# 15_1.net
KiCad netlist of a schematic drawn in EasyEDA Pro
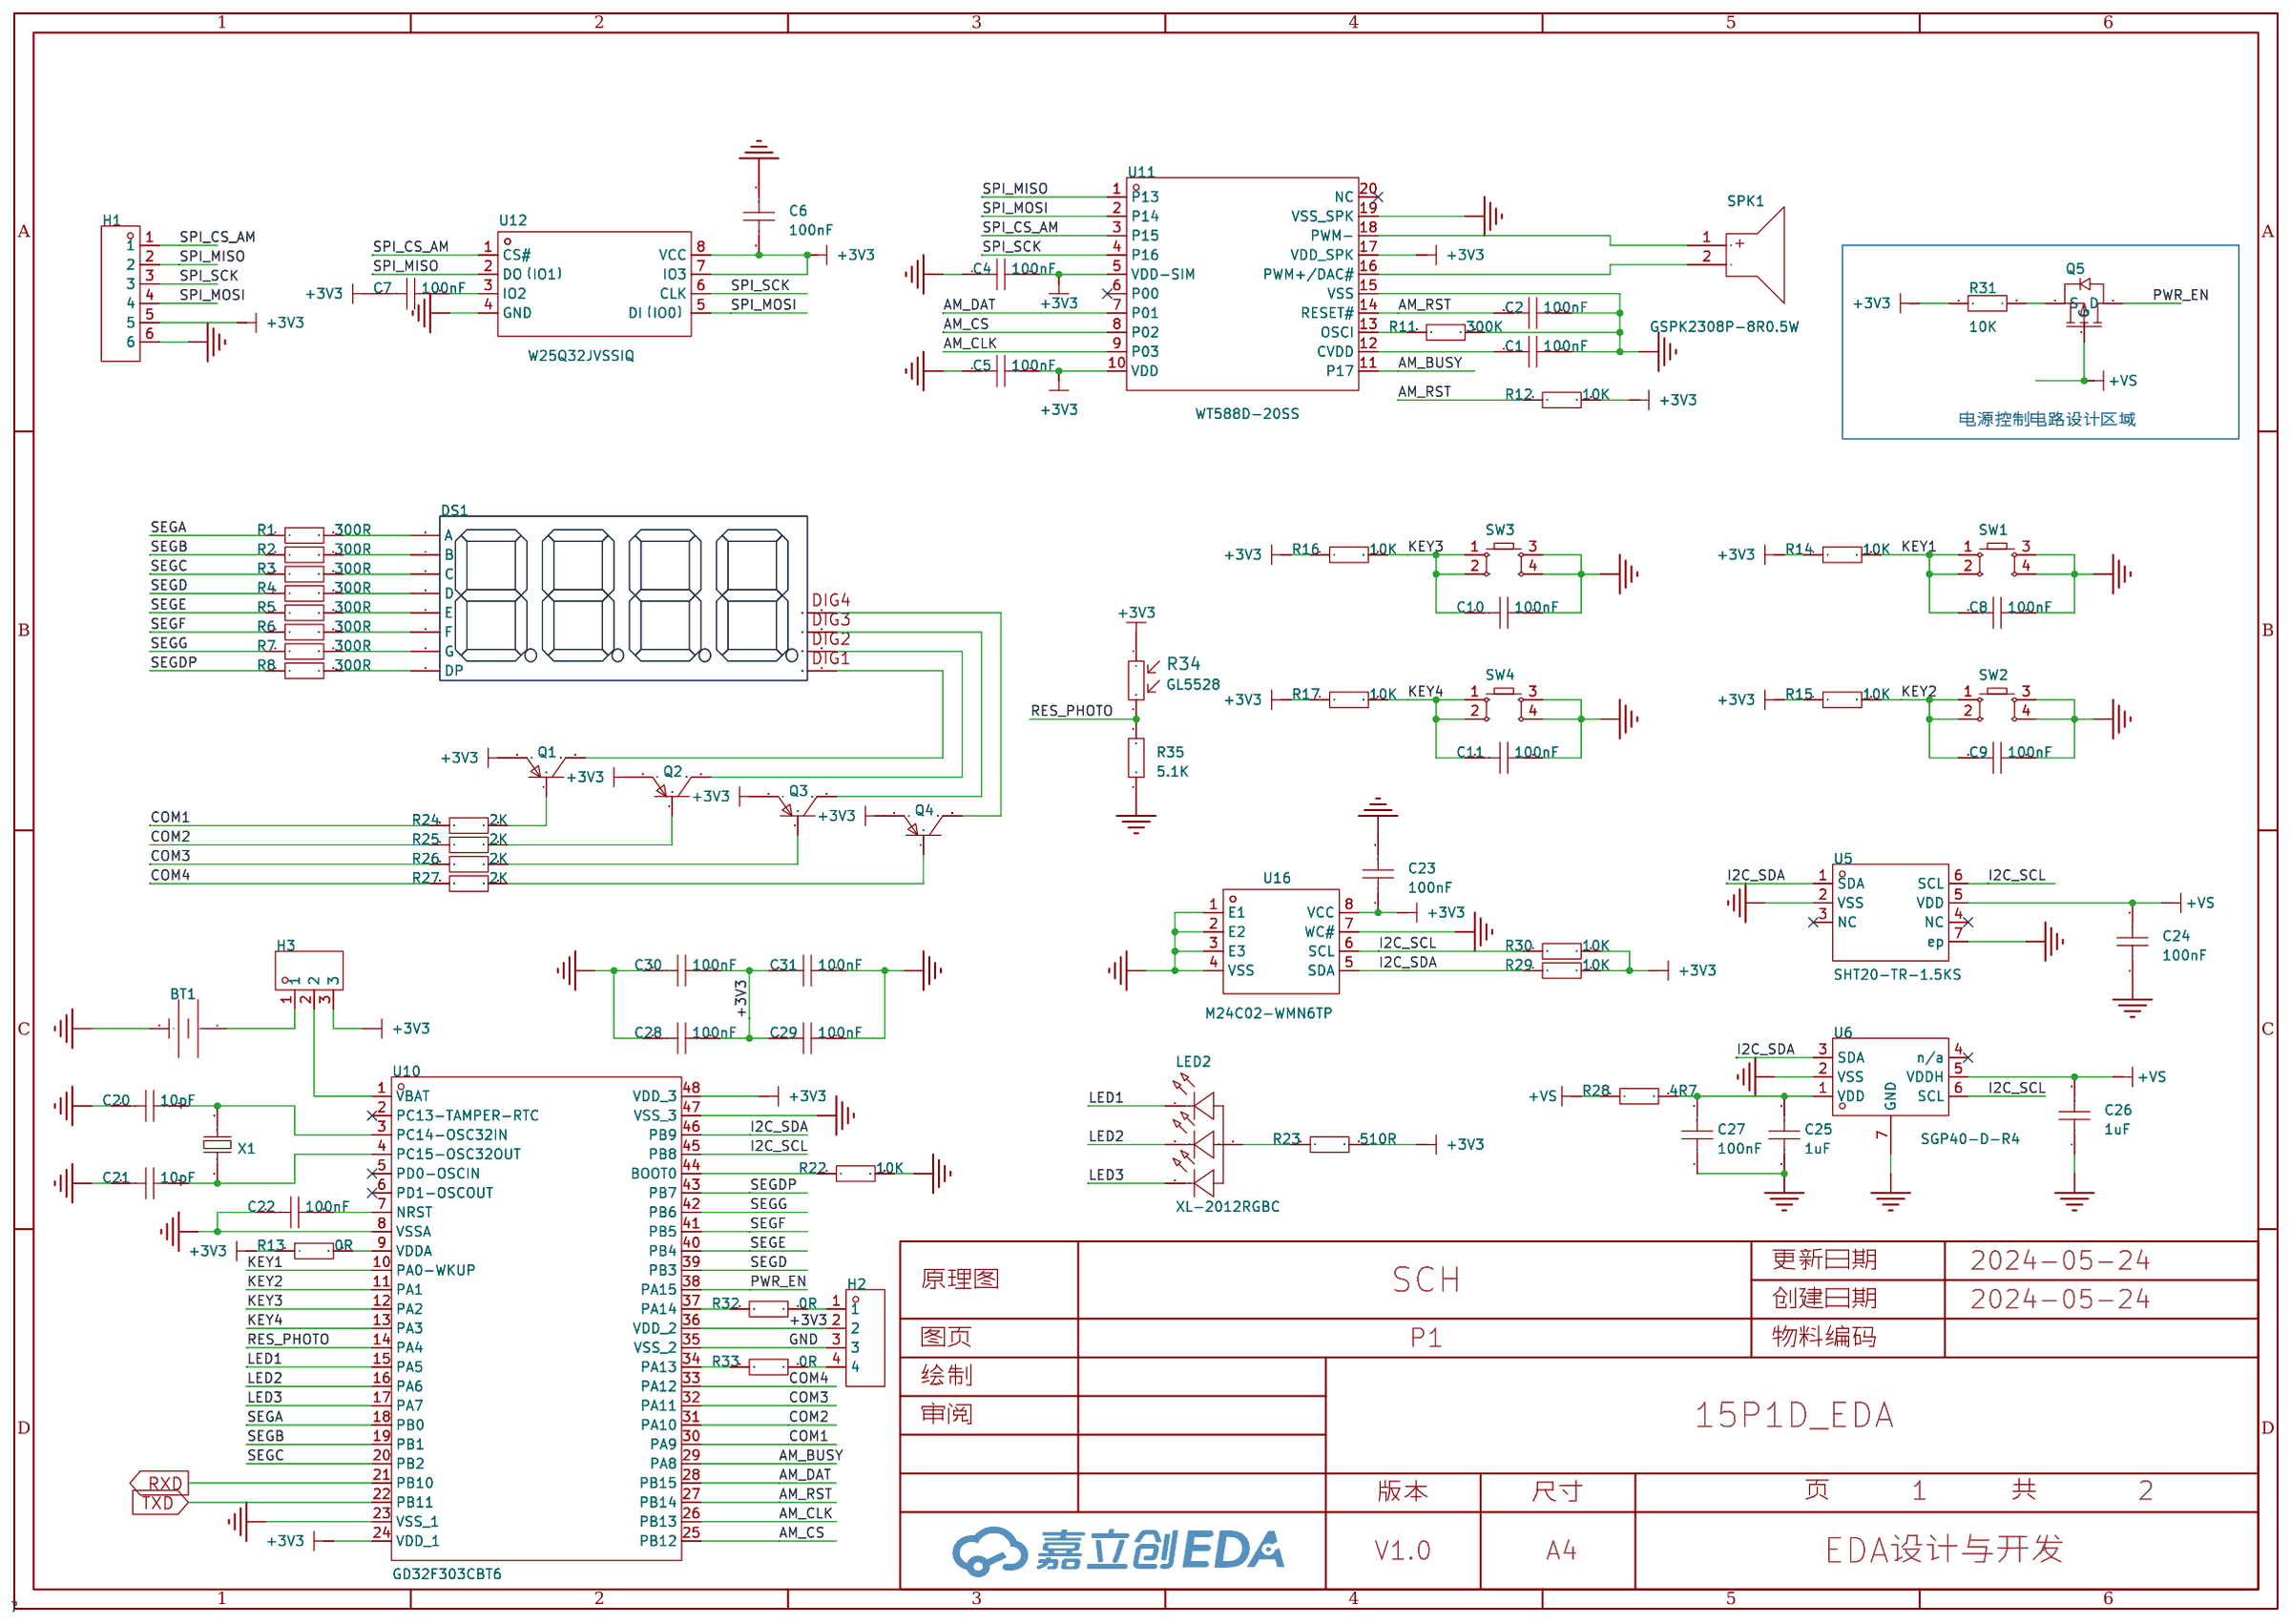
[diagram p0: P1]
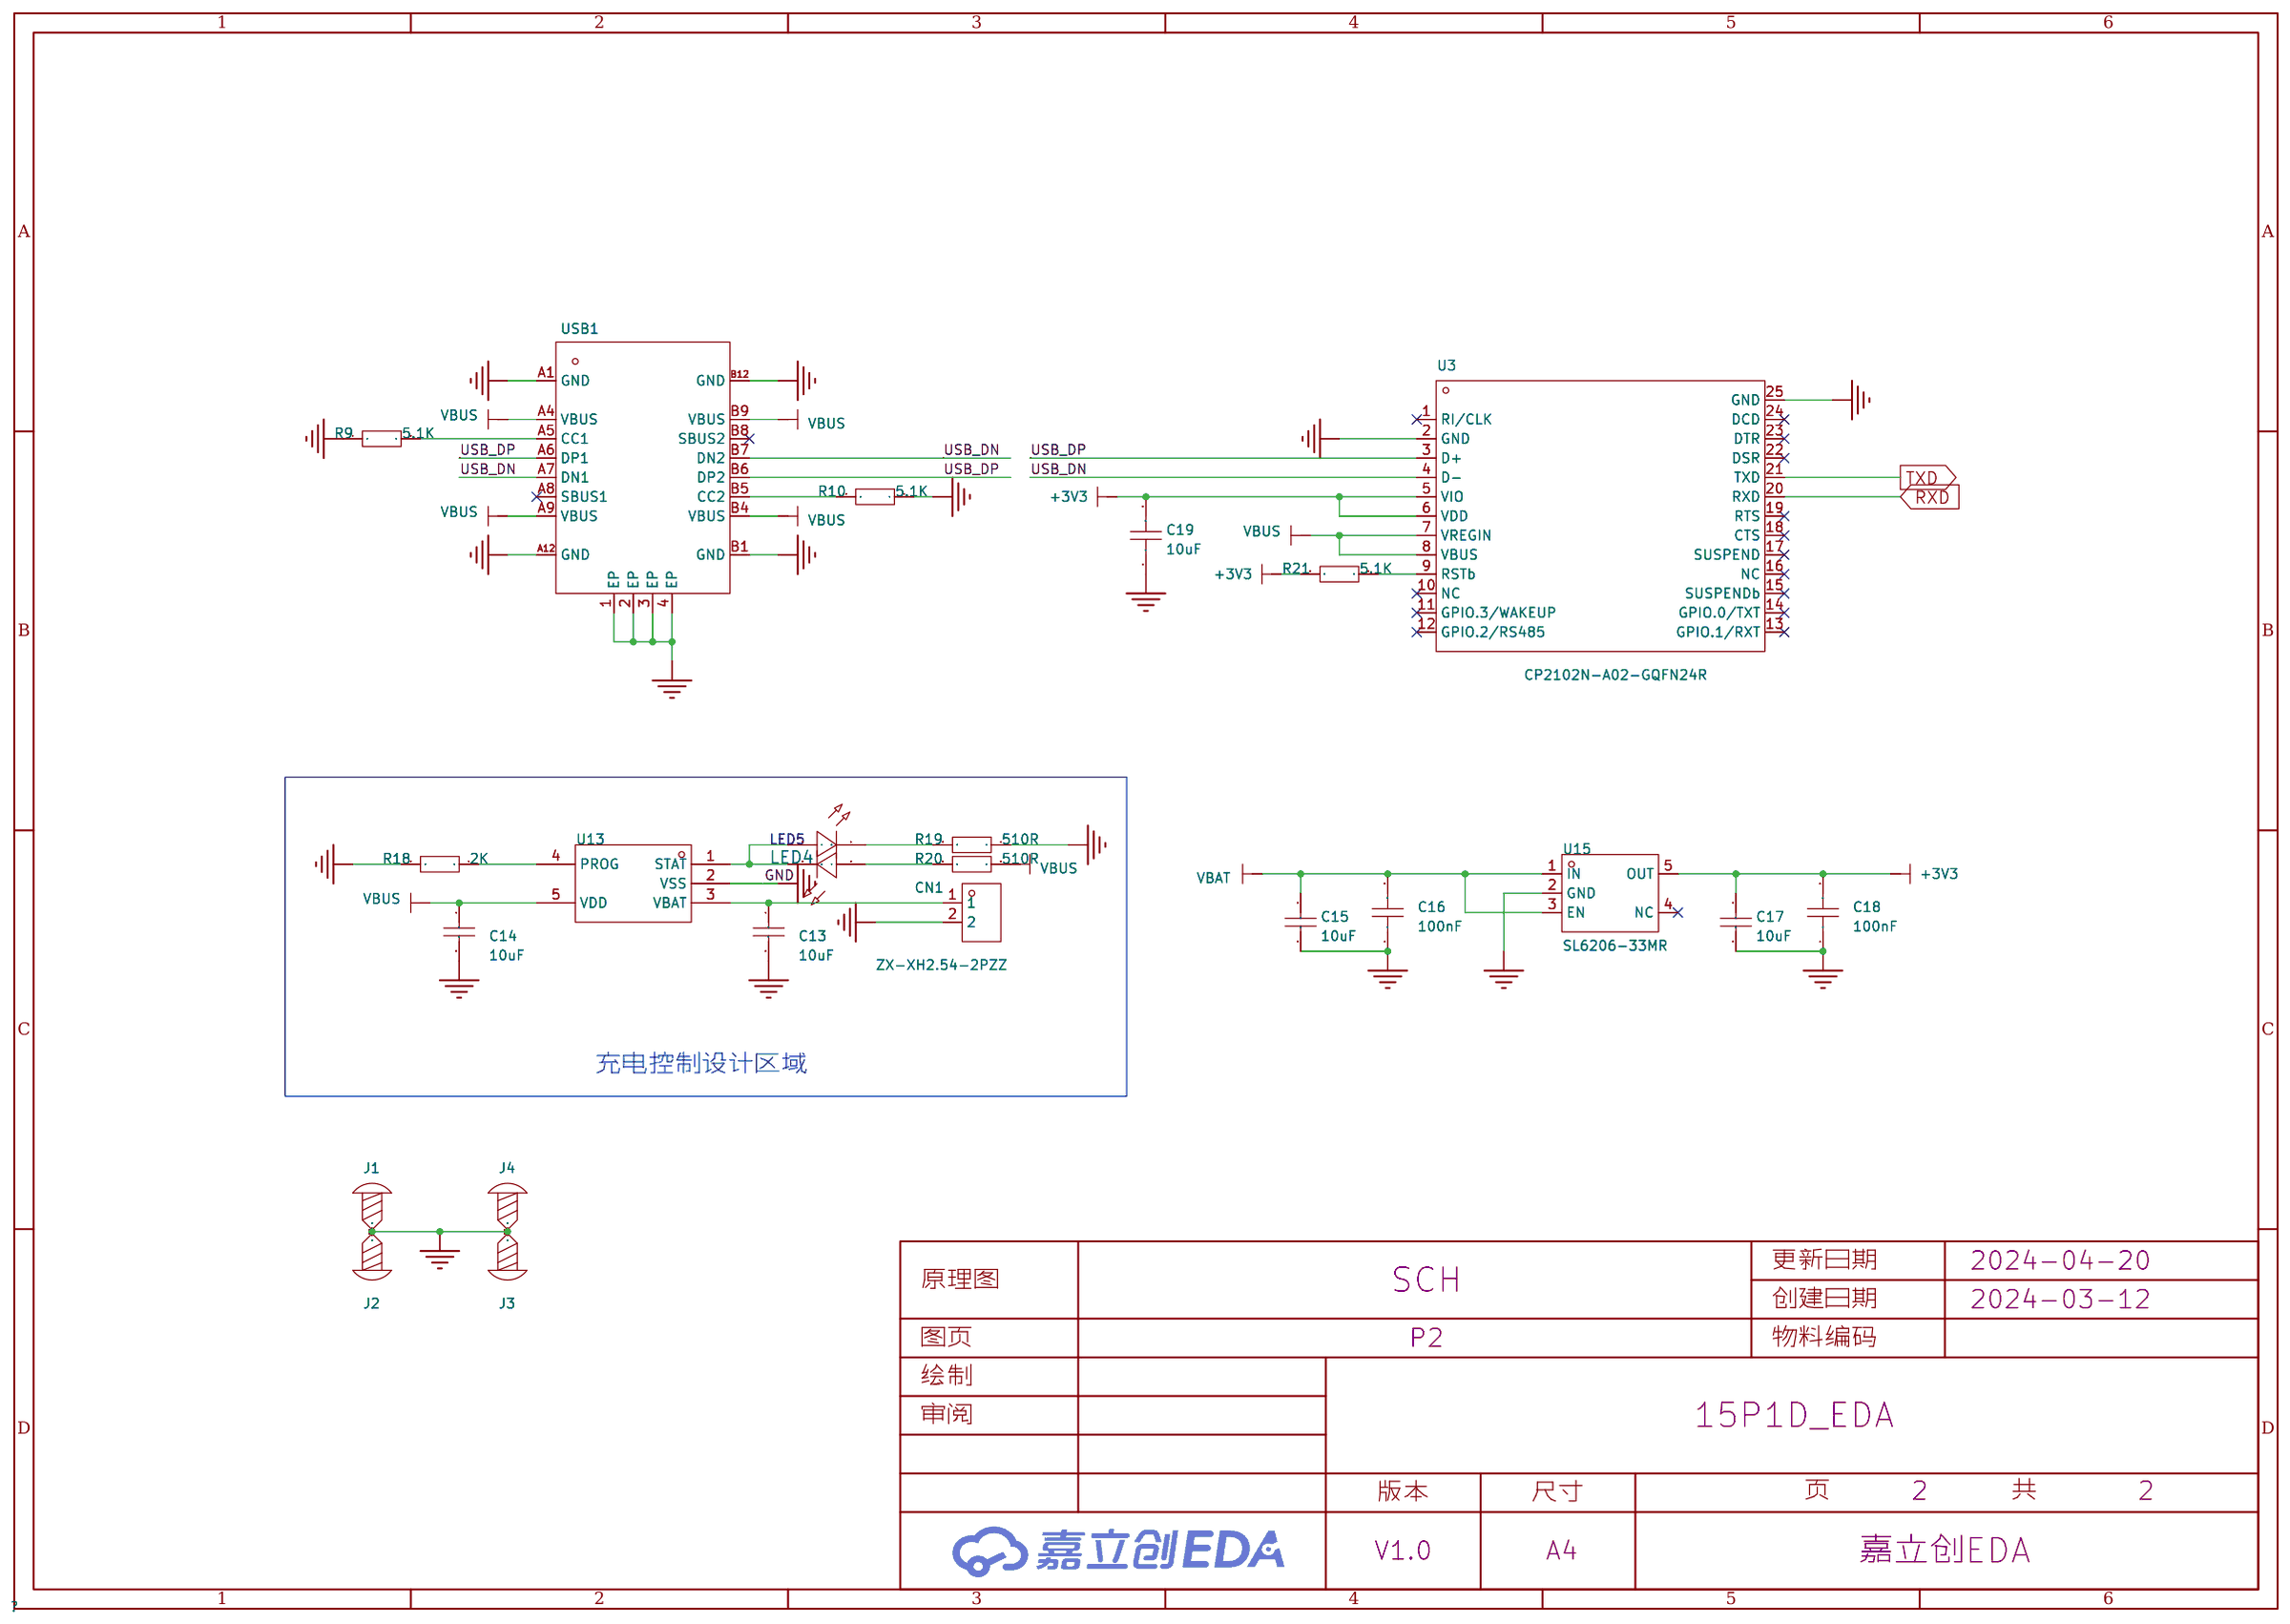
[diagram p1: P2]

(export (version "E")
  (design (tool "Eeschema 10.0.6"))
  (components
    (comp (ref "BT1")
      (value "BS-12-B3AA003")
      (footprint "easyedapro:BAT-SMD_BS-12-B3AA011")
      (description "连接器类型:电池底座;适用电池规格:CR1220;工作温度范围:-25°C~+85°C;")
      (fields (field (name "Manufacturer") "MYOUNG(美阳)"))
      (libsource (lib "easyedapro") (part "BS-12-B3AA003"))
    )
    (comp (ref "C1")
      (value "100nF")
      (footprint "easyedapro:C0805")
      (libsource (lib "easyedapro") (part "CapAcitance"))
    )
    (comp (ref "C2")
      (value "100nF")
      (footprint "easyedapro:C0805")
      (libsource (lib "easyedapro") (part "CapAcitance"))
    )
    (comp (ref "C4")
      (value "100nF")
      (footprint "easyedapro:C0805")
      (libsource (lib "easyedapro") (part "CapAcitance"))
    )
    (comp (ref "C5")
      (value "100nF")
      (footprint "easyedapro:C0805")
      (libsource (lib "easyedapro") (part "CapAcitance"))
    )
    (comp (ref "C6")
      (value "100nF")
      (footprint "easyedapro:C0805")
      (libsource (lib "easyedapro") (part "CapAcitance"))
    )
    (comp (ref "C7")
      (value "100nF")
      (footprint "easyedapro:C0805")
      (libsource (lib "easyedapro") (part "CapAcitance"))
    )
    (comp (ref "C8")
      (value "100nF")
      (footprint "easyedapro:C0805")
      (libsource (lib "easyedapro") (part "CapAcitance"))
    )
    (comp (ref "C9")
      (value "100nF")
      (footprint "easyedapro:C0805")
      (libsource (lib "easyedapro") (part "CapAcitance"))
    )
    (comp (ref "C10")
      (value "100nF")
      (footprint "easyedapro:C0805")
      (libsource (lib "easyedapro") (part "CapAcitance"))
    )
    (comp (ref "C11")
      (value "100nF")
      (footprint "easyedapro:C0805")
      (libsource (lib "easyedapro") (part "CapAcitance"))
    )
    (comp (ref "C20")
      (value "10pF")
      (footprint "easyedapro:C0805")
      (libsource (lib "easyedapro") (part "CapAcitance"))
    )
    (comp (ref "C21")
      (value "10pF")
      (footprint "easyedapro:C0805")
      (libsource (lib "easyedapro") (part "CapAcitance"))
    )
    (comp (ref "C22")
      (value "100nF")
      (footprint "easyedapro:C0805")
      (libsource (lib "easyedapro") (part "CapAcitance"))
    )
    (comp (ref "C23")
      (value "100nF")
      (footprint "easyedapro:C0805")
      (libsource (lib "easyedapro") (part "CapAcitance"))
    )
    (comp (ref "C24")
      (value "100nF")
      (footprint "easyedapro:C0805")
      (libsource (lib "easyedapro") (part "CapAcitance"))
    )
    (comp (ref "C25")
      (value "1uF")
      (footprint "easyedapro:C0805")
      (libsource (lib "easyedapro") (part "CapAcitance"))
    )
    (comp (ref "C26")
      (value "1uF")
      (footprint "easyedapro:C0805")
      (libsource (lib "easyedapro") (part "CapAcitance"))
    )
    (comp (ref "C27")
      (value "100nF")
      (footprint "easyedapro:C0805")
      (libsource (lib "easyedapro") (part "CapAcitance"))
    )
    (comp (ref "C28")
      (value "100nF")
      (footprint "easyedapro:C0805")
      (libsource (lib "easyedapro") (part "CapAcitance"))
    )
    (comp (ref "C29")
      (value "100nF")
      (footprint "easyedapro:C0805")
      (libsource (lib "easyedapro") (part "CapAcitance"))
    )
    (comp (ref "C30")
      (value "100nF")
      (footprint "easyedapro:C0805")
      (libsource (lib "easyedapro") (part "CapAcitance"))
    )
    (comp (ref "C31")
      (value "100nF")
      (footprint "easyedapro:C0805")
      (libsource (lib "easyedapro") (part "CapAcitance"))
    )
    (comp (ref "DS1")
      (value "~")
      (footprint "easyedapro:LED-SEG-TH_FJ5461AH")
      (libsource (lib "easyedapro") (part "LED_SEG_TH_0.56x4"))
    )
    (comp (ref "H1")
      (value "~")
      (footprint "easyedapro:HDR-TH_6P-P2.54-V-F")
      (libsource (lib "easyedapro") (part "Header-Female-2.54_1x6"))
    )
    (comp (ref "H2")
      (value "~")
      (footprint "easyedapro:HDR-TH_4P-P2.54-V-F")
      (libsource (lib "easyedapro") (part "2.54-1*4P母"))
    )
    (comp (ref "H3")
      (value "Jumper3")
      (footprint "easyedapro:HDR-TH_3P-P2.54-V-M-A")
      (libsource (lib "easyedapro") (part "JUMPER3"))
    )
    (comp (ref "LED2")
      (value "XL-2012RGBC")
      (footprint "easyedapro:LED-SMD_4P-L2.0-W1.3-BR")
      (fields (field (name "Manufacturer") "XINGLIGHT(成兴光)"))
      (libsource (lib "easyedapro") (part "XL-2012RGBC"))
    )
    (comp (ref "Q1")
      (value "~")
      (footprint "easyedapro:S8550P_SOT")
      (libsource (lib "easyedapro") (part "PNP"))
    )
    (comp (ref "Q2")
      (value "~")
      (footprint "easyedapro:S8550P_SOT")
      (libsource (lib "easyedapro") (part "PNP"))
    )
    (comp (ref "Q3")
      (value "~")
      (footprint "easyedapro:S8550P_SOT")
      (libsource (lib "easyedapro") (part "PNP"))
    )
    (comp (ref "Q4")
      (value "~")
      (footprint "easyedapro:S8550P_SOT")
      (libsource (lib "easyedapro") (part "PNP"))
    )
    (comp (ref "Q5")
      (value "~")
      (footprint "easyedapro:AO3401A_SOT-23-3")
      (libsource (lib "easyedapro") (part "P_MOS"))
    )
    (comp (ref "R1") (value "300R") (footprint "easyedapro:R0805") (libsource (lib "easyedapro") (part "电阻")))
    (comp (ref "R2") (value "300R") (footprint "easyedapro:R0805") (libsource (lib "easyedapro") (part "电阻")))
    (comp (ref "R3") (value "300R") (footprint "easyedapro:R0805") (libsource (lib "easyedapro") (part "电阻")))
    (comp (ref "R4") (value "300R") (footprint "easyedapro:R0805") (libsource (lib "easyedapro") (part "电阻")))
    (comp (ref "R5") (value "300R") (footprint "easyedapro:R0805") (libsource (lib "easyedapro") (part "电阻")))
    (comp (ref "R6") (value "300R") (footprint "easyedapro:R0805") (libsource (lib "easyedapro") (part "电阻")))
    (comp (ref "R7") (value "300R") (footprint "easyedapro:R0805") (libsource (lib "easyedapro") (part "电阻")))
    (comp (ref "R8") (value "300R") (footprint "easyedapro:R0805") (libsource (lib "easyedapro") (part "电阻")))
    (comp (ref "R11")
      (value "300K")
      (footprint "easyedapro:R0805")
      (libsource (lib "easyedapro") (part "电阻"))
    )
    (comp (ref "R12") (value "10K") (footprint "easyedapro:R0805") (libsource (lib "easyedapro") (part "电阻")))
    (comp (ref "R13") (value "0R") (footprint "easyedapro:R0805") (libsource (lib "easyedapro") (part "电阻")))
    (comp (ref "R14") (value "10K") (footprint "easyedapro:R0805") (libsource (lib "easyedapro") (part "电阻")))
    (comp (ref "R15") (value "10K") (footprint "easyedapro:R0805") (libsource (lib "easyedapro") (part "电阻")))
    (comp (ref "R16") (value "10K") (footprint "easyedapro:R0805") (libsource (lib "easyedapro") (part "电阻")))
    (comp (ref "R17") (value "10K") (footprint "easyedapro:R0805") (libsource (lib "easyedapro") (part "电阻")))
    (comp (ref "R22") (value "10K") (footprint "easyedapro:R0805") (libsource (lib "easyedapro") (part "电阻")))
    (comp (ref "R23")
      (value "510R")
      (footprint "easyedapro:R0805")
      (libsource (lib "easyedapro") (part "电阻"))
    )
    (comp (ref "R24") (value "2K") (footprint "easyedapro:R0805") (libsource (lib "easyedapro") (part "电阻")))
    (comp (ref "R25") (value "2K") (footprint "easyedapro:R0805") (libsource (lib "easyedapro") (part "电阻")))
    (comp (ref "R26") (value "2K") (footprint "easyedapro:R0805") (libsource (lib "easyedapro") (part "电阻")))
    (comp (ref "R27") (value "2K") (footprint "easyedapro:R0805") (libsource (lib "easyedapro") (part "电阻")))
    (comp (ref "R28") (value "4R7") (footprint "easyedapro:R0805") (libsource (lib "easyedapro") (part "电阻")))
    (comp (ref "R29") (value "10K") (footprint "easyedapro:R0805") (libsource (lib "easyedapro") (part "电阻")))
    (comp (ref "R30") (value "10K") (footprint "easyedapro:R0805") (libsource (lib "easyedapro") (part "电阻")))
    (comp (ref "R31") (value "10K") (footprint "easyedapro:R0805") (libsource (lib "easyedapro") (part "电阻")))
    (comp (ref "R32") (value "0R") (footprint "easyedapro:R0805") (libsource (lib "easyedapro") (part "电阻")))
    (comp (ref "R33") (value "0R") (footprint "easyedapro:R0805") (libsource (lib "easyedapro") (part "电阻")))
    (comp (ref "R34")
      (value "GL5528")
      (footprint "easyedapro:RES-TH_L5.1-W4.3-P3.40-D0.5")
      (description "暗电阻:1MΩ;亮电阻 @ 10Lux:8kΩ~20kΩ;光谱峰值(波长):540nm;")
      (fields (field (name "Manufacturer") "森霸"))
      (libsource (lib "easyedapro") (part "GL5528"))
    )
    (comp (ref "R35")
      (value "5.1K")
      (footprint "easyedapro:R0805")
      (libsource (lib "easyedapro") (part "电阻"))
    )
    (comp (ref "SPK1")
      (value "GSPK2308P-8R0.5W")
      (footprint "easyedapro:SPK-TH_BD23.0-P10.00-D0.8-L-RD")
      (fields (field (name "Manufacturer") "INGHAi(赢海)"))
      (libsource (lib "easyedapro") (part "GSPK2308P-8R0.5W"))
    )
    (comp (ref "SW1")
      (value "~")
      (footprint "easyedapro:Key_SMD_12x12x7.3")
      (libsource (lib "easyedapro") (part "轻触按键"))
    )
    (comp (ref "SW2")
      (value "~")
      (footprint "easyedapro:Key_SMD_12x12x7.3")
      (libsource (lib "easyedapro") (part "轻触按键"))
    )
    (comp (ref "SW3")
      (value "~")
      (footprint "easyedapro:Key_SMD_12x12x7.3")
      (libsource (lib "easyedapro") (part "轻触按键"))
    )
    (comp (ref "SW4")
      (value "~")
      (footprint "easyedapro:Key_SMD_12x12x7.3")
      (libsource (lib "easyedapro") (part "轻触按键"))
    )
    (comp (ref "U5")
      (value "SHT20-TR-1.5KS")
      (footprint "easyedapro:DFN-6_L3.0-W3.0-P0.95-TR-EP")
      (description "接口类型:I2C;")
      (fields (field (name "Manufacturer") "Sensirion(瑞士盛思锐)"))
      (libsource (lib "easyedapro") (part "SHT20"))
    )
    (comp (ref "U6")
      (value "SGP40-D-R4")
      (footprint "easyedapro:DFN-6_L2.4-W2.4-P0.80-TL-EP")
      (description "气体类型:空气质量;精度:-;")
      (fields (field (name "Manufacturer") "Sensirion(瑞士盛思锐)"))
      (libsource (lib "easyedapro") (part "SGP40-D-R4"))
    )
    (comp (ref "U10")
      (value "GD32F303CBT6")
      (footprint "easyedapro:LQFP-48_L7.0-W7.0-P0.50-LS9.0-BL")
      (description "CPU内核:CM4;程序存储容量:128KB;RAM总容量:32KB;GPIO端口数量:37;工作电压范围:-;CPU最大主频:120MHz;程序存储器类型:FLASH;")
      (fields (field (name "Manufacturer") "GigaDevice(兆易创新)"))
      (libsource (lib "easyedapro") (part "GD32F303CBT6"))
    )
    (comp (ref "U11")
      (value "WT588D-20SS")
      (footprint "easyedapro:SSOP-20_L7.2-W5.3-P0.65-LS7.8-BL")
      (description "高品质语音芯片")
      (fields (field (name "Manufacturer") "WT(唯创知音)"))
      (libsource (lib "easyedapro") (part "WT588D"))
    )
    (comp (ref "U12")
      (value "W25Q32JVSSIQ")
      (footprint "easyedapro:SOIC-8_L5.3-W5.3-P1.27-LS8.0-BL")
      (description "接口类型:SPI;存储容量:32Mbit;")
      (fields (field (name "Manufacturer") "WINBOND(华邦)"))
      (libsource (lib "easyedapro") (part "W25Q32JVSSIQ"))
    )
    (comp (ref "U16")
      (value "M24C02-WMN6TP")
      (footprint "easyedapro:SOIC-8_L4.9-W3.9-P1.27-LS6.0-BL")
      (description "接口类型:I2C;存储容量:2Kbit;")
      (fields (field (name "Manufacturer") "ST(意法半导体)"))
      (libsource (lib "easyedapro") (part "M24C02-WMN6TP"))
    )
    (comp (ref "X1")
      (value "32.768kHz")
      (footprint "easyedapro:FC-135R_L3.2-W1.5")
      (description "晶振类型:贴片晶振;频率:32.768kHz;常温频差:±20ppm;外接负载电容:12.5pF;")
      (fields (field (name "Manufacturer Part") "Q13FC13500004") (field (name "Manufacturer") "EPSON(爱普生)"))
      (libsource (lib "easyedapro") (part "Q13FC1350000400"))
    )
    (comp (ref "C13")
      (value "10uF")
      (footprint "easyedapro:C1206")
      (description "容值:10uF;精度:±10%;额定电压:50V;材质(温度系数):X5R;")
      (fields
        (field (name "Manufacturer Part") "CL31A106KBHNNNE")
        (field (name "Manufacturer") "SAMSUNG(三星)")
      )
      (libsource (lib "easyedapro") (part "CL31A106KBHNNNE"))
    )
    (comp (ref "C14")
      (value "10uF")
      (footprint "easyedapro:C1206")
      (description "容值:10uF;精度:±10%;额定电压:50V;材质(温度系数):X5R;")
      (fields
        (field (name "Manufacturer Part") "CL31A106KBHNNNE")
        (field (name "Manufacturer") "SAMSUNG(三星)")
      )
      (libsource (lib "easyedapro") (part "CL31A106KBHNNNE"))
    )
    (comp (ref "C15")
      (value "10uF")
      (footprint "easyedapro:C1206")
      (description "容值:10uF;精度:±10%;额定电压:50V;材质(温度系数):X5R;")
      (fields
        (field (name "Manufacturer Part") "CL31A106KBHNNNE")
        (field (name "Manufacturer") "SAMSUNG(三星)")
      )
      (libsource (lib "easyedapro") (part "CL31A106KBHNNNE"))
    )
    (comp (ref "C16")
      (value "100nF")
      (footprint "easyedapro:C0805")
      (libsource (lib "easyedapro") (part "CapAcitance"))
    )
    (comp (ref "C17")
      (value "10uF")
      (footprint "easyedapro:C1206")
      (description "容值:10uF;精度:±10%;额定电压:50V;材质(温度系数):X5R;")
      (fields
        (field (name "Manufacturer Part") "CL31A106KBHNNNE")
        (field (name "Manufacturer") "SAMSUNG(三星)")
      )
      (libsource (lib "easyedapro") (part "CL31A106KBHNNNE"))
    )
    (comp (ref "C18")
      (value "100nF")
      (footprint "easyedapro:C0805")
      (libsource (lib "easyedapro") (part "CapAcitance"))
    )
    (comp (ref "C19")
      (value "10uF")
      (footprint "easyedapro:C0805")
      (libsource (lib "easyedapro") (part "CapAcitance"))
    )
    (comp (ref "CN1")
      (value "ZX-XH2.54-2PZZ")
      (footprint "easyedapro:CONN-TH_2P-P2.50_HX25003-2A")
      (fields (field (name "Manufacturer") "Megastar(兆星)"))
      (libsource (lib "easyedapro") (part "ZX-XH2.54-2PZZ"))
    )
    (comp (ref "J1") (value "~") (footprint "easyedapro:M2螺丝") (libsource (lib "easyedapro") (part "螺丝孔")))
    (comp (ref "J2") (value "~") (footprint "easyedapro:M2螺丝") (libsource (lib "easyedapro") (part "螺丝孔")))
    (comp (ref "J3") (value "~") (footprint "easyedapro:M2螺丝") (libsource (lib "easyedapro") (part "螺丝孔")))
    (comp (ref "J4") (value "~") (footprint "easyedapro:M2螺丝") (libsource (lib "easyedapro") (part "螺丝孔")))
    (comp (ref "LED4")
      (value "~")
      (footprint "easyedapro:LED_0805")
      (libsource (lib "easyedapro") (part "LED_R"))
    )
    (comp (ref "LED5")
      (value "~")
      (footprint "easyedapro:LED_0805")
      (libsource (lib "easyedapro") (part "LED_G"))
    )
    (comp (ref "R9") (value "5.1K") (footprint "easyedapro:R0805") (libsource (lib "easyedapro") (part "电阻")))
    (comp (ref "R10")
      (value "5.1K")
      (footprint "easyedapro:R0805")
      (libsource (lib "easyedapro") (part "电阻"))
    )
    (comp (ref "R18") (value "2K") (footprint "easyedapro:R0805") (libsource (lib "easyedapro") (part "电阻")))
    (comp (ref "R19")
      (value "510R")
      (footprint "easyedapro:R0805")
      (libsource (lib "easyedapro") (part "电阻"))
    )
    (comp (ref "R20")
      (value "510R")
      (footprint "easyedapro:R0805")
      (libsource (lib "easyedapro") (part "电阻"))
    )
    (comp (ref "R21")
      (value "5.1K")
      (footprint "easyedapro:R0805")
      (libsource (lib "easyedapro") (part "电阻"))
    )
    (comp (ref "U3")
      (value "CP2102N-A02-GQFN24R")
      (footprint "easyedapro:QFN-24_L4.0-W4.0-P0.50-TL-EP2.6")
      (description "应用功能:USB转UART;接口协议:UART;")
      (fields (field (name "Manufacturer") "SKYWORKS/SILICON LABS(芯科)"))
      (libsource (lib "easyedapro") (part "CP2102N-A02-GQFN24R"))
    )
    (comp (ref "U13")
      (value "~")
      (footprint "easyedapro:SOP_BCON")
      (libsource (lib "easyedapro") (part "BCON"))
    )
    (comp (ref "U15")
      (value "SL6206-33MR")
      (footprint "easyedapro:SOT-23-5_L2.9-W1.6-P0.95-LS2.8-BL")
      (description "输出类型:-;")
      (fields (field (name "Manufacturer") "Slkor(萨科微)"))
      (libsource (lib "easyedapro") (part "SL6206-33MR"))
    )
    (comp (ref "USB1")
      (value "~")
      (footprint "easyedapro:USB_TYPE-C-16P")
      (libsource (lib "easyedapro") (part "USB_TYPE-C-16P"))
    )
  )
  (nets
    (net (code "1") (name "+3V3") (class "Default")
      (node (ref "C17") (pin "2") (pinfunction "2_2") (pintype "input"))
      (node (ref "C18") (pin "2") (pinfunction "2_2") (pintype "input"))
      (node (ref "C19") (pin "2") (pinfunction "2_2") (pintype "input"))
      (node (ref "C23") (pin "1") (pinfunction "1_1") (pintype "input"))
      (node (ref "C28") (pin "1") (pinfunction "1_1") (pintype "input"))
      (node (ref "C29") (pin "2") (pinfunction "2_2") (pintype "input"))
      (node (ref "C30") (pin "1") (pinfunction "1_1") (pintype "input"))
      (node (ref "C31") (pin "2") (pinfunction "2_2") (pintype "input"))
      (node (ref "C4") (pin "2") (pinfunction "2_2") (pintype "input"))
      (node (ref "C5") (pin "2") (pinfunction "2_2") (pintype "input"))
      (node (ref "C6") (pin "2") (pinfunction "2_2") (pintype "input"))
      (node (ref "C7") (pin "1") (pinfunction "1_1") (pintype "input"))
      (node (ref "H1") (pin "5") (pinfunction "5_5") (pintype "unspecified"))
      (node (ref "H2") (pin "2") (pinfunction "2_2") (pintype "unspecified"))
      (node (ref "H3") (pin "3") (pinfunction "3_3") (pintype "input"))
      (node (ref "Q1") (pin "2") (pinfunction "E_2") (pintype "input"))
      (node (ref "Q2") (pin "2") (pinfunction "E_2") (pintype "input"))
      (node (ref "Q3") (pin "2") (pinfunction "E_2") (pintype "input"))
      (node (ref "Q4") (pin "2") (pinfunction "E_2") (pintype "input"))
      (node (ref "R12") (pin "2") (pinfunction "2_2") (pintype "input"))
      (node (ref "R13") (pin "1") (pinfunction "1_1") (pintype "input"))
      (node (ref "R14") (pin "1") (pinfunction "1_1") (pintype "input"))
      (node (ref "R15") (pin "1") (pinfunction "1_1") (pintype "input"))
      (node (ref "R16") (pin "1") (pinfunction "1_1") (pintype "input"))
      (node (ref "R17") (pin "1") (pinfunction "1_1") (pintype "input"))
      (node (ref "R21") (pin "2") (pinfunction "2_2") (pintype "input"))
      (node (ref "R23") (pin "2") (pinfunction "2_2") (pintype "input"))
      (node (ref "R29") (pin "2") (pinfunction "2_2") (pintype "input"))
      (node (ref "R30") (pin "2") (pinfunction "2_2") (pintype "input"))
      (node (ref "R31") (pin "2") (pinfunction "2_2") (pintype "input"))
      (node (ref "R34") (pin "1") (pinfunction "1_1") (pintype "input"))
      (node (ref "U10") (pin "24") (pinfunction "VDD_1_24") (pintype "unspecified"))
      (node (ref "U10") (pin "36") (pinfunction "VDD_2_36") (pintype "unspecified"))
      (node (ref "U10") (pin "48") (pinfunction "VDD_3_48") (pintype "unspecified"))
      (node (ref "U11") (pin "10") (pinfunction "VDD_10") (pintype "input"))
      (node (ref "U11") (pin "17") (pinfunction "VDD_SPK_17") (pintype "input"))
      (node (ref "U11") (pin "5") (pinfunction "VDD-SIM_5") (pintype "input"))
      (node (ref "U12") (pin "7") (pinfunction "IO3_7") (pintype "unspecified"))
      (node (ref "U12") (pin "8") (pinfunction "VCC_8") (pintype "unspecified"))
      (node (ref "U15") (pin "5") (pinfunction "OUT_5") (pintype "unspecified"))
      (node (ref "U16") (pin "8") (pinfunction "VCC_8") (pintype "unspecified"))
      (node (ref "U3") (pin "5") (pinfunction "VIO_5") (pintype "unspecified"))
      (node (ref "U3") (pin "6") (pinfunction "VDD_6") (pintype "unspecified"))
    )
    (net (code "2") (name "+VS") (class "Default")
      (node (ref "C24") (pin "2") (pinfunction "2_2") (pintype "input"))
      (node (ref "C26") (pin "2") (pinfunction "2_2") (pintype "input"))
      (node (ref "Q5") (pin "1") (pinfunction "G_1") (pintype "input"))
      (node (ref "R28") (pin "1") (pinfunction "1_1") (pintype "input"))
      (node (ref "U5") (pin "5") (pinfunction "VDD_5") (pintype "unspecified"))
      (node (ref "U6") (pin "5") (pinfunction "VDDH_5") (pintype "unspecified"))
    )
    (net (code "3") (name "AM_BUSY") (class "Default")
      (node (ref "U10") (pin "29") (pinfunction "PA8_29") (pintype "unspecified"))
      (node (ref "U11") (pin "11") (pinfunction "P17_11") (pintype "input"))
    )
    (net (code "4") (name "AM_CLK") (class "Default")
      (node (ref "U10") (pin "26") (pinfunction "PB13_26") (pintype "unspecified"))
      (node (ref "U11") (pin "9") (pinfunction "P03_9") (pintype "input"))
    )
    (net (code "5") (name "AM_CS") (class "Default")
      (node (ref "U10") (pin "25") (pinfunction "PB12_25") (pintype "unspecified"))
      (node (ref "U11") (pin "8") (pinfunction "P02_8") (pintype "input"))
    )
    (net (code "6") (name "AM_DAT") (class "Default")
      (node (ref "U10") (pin "28") (pinfunction "PB15_28") (pintype "unspecified"))
      (node (ref "U11") (pin "7") (pinfunction "P01_7") (pintype "input"))
    )
    (net (code "7") (name "AM_RST") (class "Default")
      (node (ref "C2") (pin "1") (pinfunction "1_1") (pintype "input"))
      (node (ref "R12") (pin "1") (pinfunction "1_1") (pintype "input"))
      (node (ref "U10") (pin "27") (pinfunction "PB14_27") (pintype "unspecified"))
      (node (ref "U11") (pin "14") (pinfunction "RESET#_14") (pintype "input"))
    )
    (net (code "8") (name "COM1") (class "Default")
      (node (ref "R24") (pin "1") (pinfunction "1_1") (pintype "input"))
      (node (ref "U10") (pin "30") (pinfunction "PA9_30") (pintype "unspecified"))
    )
    (net (code "9") (name "COM2") (class "Default")
      (node (ref "R25") (pin "1") (pinfunction "1_1") (pintype "input"))
      (node (ref "U10") (pin "31") (pinfunction "PA10_31") (pintype "unspecified"))
    )
    (net (code "10") (name "COM3") (class "Default")
      (node (ref "R26") (pin "1") (pinfunction "1_1") (pintype "input"))
      (node (ref "U10") (pin "32") (pinfunction "PA11_32") (pintype "unspecified"))
    )
    (net (code "11") (name "COM4") (class "Default")
      (node (ref "R27") (pin "1") (pinfunction "1_1") (pintype "input"))
      (node (ref "U10") (pin "33") (pinfunction "PA12_33") (pintype "unspecified"))
    )
    (net (code "12") (name "GND") (class "Default")
      (node (ref "BT1") (pin "2") (pinfunction "-_2") (pintype "unspecified"))
      (node (ref "C1") (pin "2") (pinfunction "2_2") (pintype "input"))
      (node (ref "C10") (pin "2") (pinfunction "2_2") (pintype "input"))
      (node (ref "C11") (pin "2") (pinfunction "2_2") (pintype "input"))
      (node (ref "C13") (pin "2") (pinfunction "2_2") (pintype "input"))
      (node (ref "C14") (pin "2") (pinfunction "2_2") (pintype "input"))
      (node (ref "C15") (pin "1") (pinfunction "1_1") (pintype "input"))
      (node (ref "C16") (pin "1") (pinfunction "1_1") (pintype "input"))
      (node (ref "C17") (pin "1") (pinfunction "1_1") (pintype "input"))
      (node (ref "C18") (pin "1") (pinfunction "1_1") (pintype "input"))
      (node (ref "C19") (pin "1") (pinfunction "1_1") (pintype "input"))
      (node (ref "C2") (pin "2") (pinfunction "2_2") (pintype "input"))
      (node (ref "C20") (pin "1") (pinfunction "1_1") (pintype "input"))
      (node (ref "C21") (pin "1") (pinfunction "1_1") (pintype "input"))
      (node (ref "C22") (pin "1") (pinfunction "1_1") (pintype "input"))
      (node (ref "C23") (pin "2") (pinfunction "2_2") (pintype "input"))
      (node (ref "C24") (pin "1") (pinfunction "1_1") (pintype "input"))
      (node (ref "C25") (pin "1") (pinfunction "1_1") (pintype "input"))
      (node (ref "C26") (pin "1") (pinfunction "1_1") (pintype "input"))
      (node (ref "C27") (pin "1") (pinfunction "1_1") (pintype "input"))
      (node (ref "C28") (pin "2") (pinfunction "2_2") (pintype "input"))
      (node (ref "C29") (pin "1") (pinfunction "1_1") (pintype "input"))
      (node (ref "C30") (pin "2") (pinfunction "2_2") (pintype "input"))
      (node (ref "C31") (pin "1") (pinfunction "1_1") (pintype "input"))
      (node (ref "C4") (pin "1") (pinfunction "1_1") (pintype "input"))
      (node (ref "C5") (pin "1") (pinfunction "1_1") (pintype "input"))
      (node (ref "C6") (pin "1") (pinfunction "1_1") (pintype "input"))
      (node (ref "C8") (pin "2") (pinfunction "2_2") (pintype "input"))
      (node (ref "C9") (pin "2") (pinfunction "2_2") (pintype "input"))
      (node (ref "CN1") (pin "2") (pinfunction "2_2") (pintype "unspecified"))
      (node (ref "H1") (pin "6") (pinfunction "6_6") (pintype "unspecified"))
      (node (ref "H2") (pin "3") (pinfunction "3_3") (pintype "unspecified"))
      (node (ref "J1") (pin "1") (pinfunction "1_1") (pintype "input"))
      (node (ref "J2") (pin "1") (pinfunction "1_1") (pintype "input"))
      (node (ref "J3") (pin "1") (pinfunction "1_1") (pintype "input"))
      (node (ref "J4") (pin "1") (pinfunction "1_1") (pintype "input"))
      (node (ref "R10") (pin "1") (pinfunction "1_1") (pintype "input"))
      (node (ref "R11") (pin "2") (pinfunction "2_2") (pintype "input"))
      (node (ref "R18") (pin "2") (pinfunction "2_2") (pintype "input"))
      (node (ref "R19") (pin "1") (pinfunction "1_1") (pintype "input"))
      (node (ref "R22") (pin "2") (pinfunction "2_2") (pintype "input"))
      (node (ref "R35") (pin "2") (pinfunction "2_2") (pintype "input"))
      (node (ref "R9") (pin "1") (pinfunction "1_1") (pintype "input"))
      (node (ref "SW1") (pin "3") (pinfunction "3_3") (pintype "input"))
      (node (ref "SW1") (pin "4") (pinfunction "4_4") (pintype "input"))
      (node (ref "SW2") (pin "3") (pinfunction "3_3") (pintype "input"))
      (node (ref "SW2") (pin "4") (pinfunction "4_4") (pintype "input"))
      (node (ref "SW3") (pin "3") (pinfunction "3_3") (pintype "input"))
      (node (ref "SW3") (pin "4") (pinfunction "4_4") (pintype "input"))
      (node (ref "SW4") (pin "3") (pinfunction "3_3") (pintype "input"))
      (node (ref "SW4") (pin "4") (pinfunction "4_4") (pintype "input"))
      (node (ref "U10") (pin "23") (pinfunction "VSS_1_23") (pintype "unspecified"))
      (node (ref "U10") (pin "35") (pinfunction "VSS_2_35") (pintype "unspecified"))
      (node (ref "U10") (pin "47") (pinfunction "VSS_3_47") (pintype "unspecified"))
      (node (ref "U10") (pin "8") (pinfunction "VSSA_8") (pintype "unspecified"))
      (node (ref "U11") (pin "15") (pinfunction "VSS_15") (pintype "input"))
      (node (ref "U11") (pin "19") (pinfunction "VSS_SPK_19") (pintype "input"))
      (node (ref "U12") (pin "4") (pinfunction "GND_4") (pintype "unspecified"))
      (node (ref "U13") (pin "2") (pinfunction "VSS_2") (pintype "input"))
      (node (ref "U15") (pin "2") (pinfunction "GND_2") (pintype "unspecified"))
      (node (ref "U16") (pin "1") (pinfunction "E1_1") (pintype "unspecified"))
      (node (ref "U16") (pin "2") (pinfunction "E2_2") (pintype "unspecified"))
      (node (ref "U16") (pin "3") (pinfunction "E3_3") (pintype "unspecified"))
      (node (ref "U16") (pin "4") (pinfunction "VSS_4") (pintype "unspecified"))
      (node (ref "U16") (pin "7") (pinfunction "WC#_7") (pintype "unspecified"))
      (node (ref "U3") (pin "2") (pinfunction "GND_2") (pintype "unspecified"))
      (node (ref "U3") (pin "25") (pinfunction "GND_25") (pintype "unspecified"))
      (node (ref "U5") (pin "2") (pinfunction "VSS_2") (pintype "unspecified"))
      (node (ref "U5") (pin "7") (pinfunction "ep_7") (pintype "unspecified"))
      (node (ref "U6") (pin "2") (pinfunction "VSS_2") (pintype "unspecified"))
      (node (ref "U6") (pin "7") (pinfunction "GND_7") (pintype "unspecified"))
      (node (ref "USB1") (pin "1") (pinfunction "EP_1") (pintype "input"))
      (node (ref "USB1") (pin "2") (pinfunction "EP_2") (pintype "input"))
      (node (ref "USB1") (pin "3") (pinfunction "EP_3") (pintype "input"))
      (node (ref "USB1") (pin "4") (pinfunction "EP_4") (pintype "input"))
      (node (ref "USB1") (pin "A1") (pinfunction "GND_A1") (pintype "input"))
      (node (ref "USB1") (pin "A12") (pinfunction "GND_A12") (pintype "input"))
      (node (ref "USB1") (pin "B1") (pinfunction "GND_B1") (pintype "input"))
      (node (ref "USB1") (pin "B12") (pinfunction "GND_B12") (pintype "input"))
    )
    (net (code "13") (name "I2C_SCL") (class "Default")
      (node (ref "R30") (pin "1") (pinfunction "1_1") (pintype "input"))
      (node (ref "U10") (pin "45") (pinfunction "PB8_45") (pintype "unspecified"))
      (node (ref "U16") (pin "6") (pinfunction "SCL_6") (pintype "unspecified"))
      (node (ref "U5") (pin "6") (pinfunction "SCL_6") (pintype "unspecified"))
      (node (ref "U6") (pin "6") (pinfunction "SCL_6") (pintype "unspecified"))
    )
    (net (code "14") (name "I2C_SDA") (class "Default")
      (node (ref "R29") (pin "1") (pinfunction "1_1") (pintype "input"))
      (node (ref "U10") (pin "46") (pinfunction "PB9_46") (pintype "unspecified"))
      (node (ref "U16") (pin "5") (pinfunction "SDA_5") (pintype "unspecified"))
      (node (ref "U5") (pin "1") (pinfunction "SDA_1") (pintype "unspecified"))
      (node (ref "U6") (pin "3") (pinfunction "SDA_3") (pintype "unspecified"))
    )
    (net (code "15") (name "KEY1") (class "Default")
      (node (ref "C8") (pin "1") (pinfunction "1_1") (pintype "input"))
      (node (ref "R14") (pin "2") (pinfunction "2_2") (pintype "input"))
      (node (ref "SW1") (pin "1") (pinfunction "1_1") (pintype "input"))
      (node (ref "SW1") (pin "2") (pinfunction "2_2") (pintype "input"))
      (node (ref "U10") (pin "10") (pinfunction "PA0-WKUP_10") (pintype "unspecified"))
    )
    (net (code "16") (name "KEY2") (class "Default")
      (node (ref "C9") (pin "1") (pinfunction "1_1") (pintype "input"))
      (node (ref "R15") (pin "2") (pinfunction "2_2") (pintype "input"))
      (node (ref "SW2") (pin "1") (pinfunction "1_1") (pintype "input"))
      (node (ref "SW2") (pin "2") (pinfunction "2_2") (pintype "input"))
      (node (ref "U10") (pin "11") (pinfunction "PA1_11") (pintype "unspecified"))
    )
    (net (code "17") (name "KEY3") (class "Default")
      (node (ref "C10") (pin "1") (pinfunction "1_1") (pintype "input"))
      (node (ref "R16") (pin "2") (pinfunction "2_2") (pintype "input"))
      (node (ref "SW3") (pin "1") (pinfunction "1_1") (pintype "input"))
      (node (ref "SW3") (pin "2") (pinfunction "2_2") (pintype "input"))
      (node (ref "U10") (pin "12") (pinfunction "PA2_12") (pintype "unspecified"))
    )
    (net (code "18") (name "KEY4") (class "Default")
      (node (ref "C11") (pin "1") (pinfunction "1_1") (pintype "input"))
      (node (ref "R17") (pin "2") (pinfunction "2_2") (pintype "input"))
      (node (ref "SW4") (pin "1") (pinfunction "1_1") (pintype "input"))
      (node (ref "SW4") (pin "2") (pinfunction "2_2") (pintype "input"))
      (node (ref "U10") (pin "13") (pinfunction "PA3_13") (pintype "unspecified"))
    )
    (net (code "19") (name "LED1") (class "Default")
      (node (ref "LED2") (pin "1") (pinfunction "1_1") (pintype "unspecified"))
      (node (ref "U10") (pin "15") (pinfunction "PA5_15") (pintype "unspecified"))
    )
    (net (code "20") (name "LED2") (class "Default")
      (node (ref "LED2") (pin "2") (pinfunction "2_2") (pintype "unspecified"))
      (node (ref "U10") (pin "16") (pinfunction "PA6_16") (pintype "unspecified"))
    )
    (net (code "21") (name "LED3") (class "Default")
      (node (ref "LED2") (pin "4") (pinfunction "4_4") (pintype "unspecified"))
      (node (ref "U10") (pin "17") (pinfunction "PA7_17") (pintype "unspecified"))
    )
    (net (code "22") (name "Net-(BT1-+)") (class "Default")
      (node (ref "BT1") (pin "1") (pinfunction "+_1") (pintype "unspecified"))
      (node (ref "H3") (pin "1") (pinfunction "1_1") (pintype "input"))
    )
    (net (code "23") (name "Net-(DS1-A)") (class "Default")
      (node (ref "DS1") (pin "11") (pinfunction "A_11") (pintype "input"))
      (node (ref "R1") (pin "2") (pinfunction "2_2") (pintype "input"))
    )
    (net (code "24") (name "Net-(DS1-B)") (class "Default")
      (node (ref "DS1") (pin "7") (pinfunction "B_7") (pintype "input"))
      (node (ref "R2") (pin "2") (pinfunction "2_2") (pintype "input"))
    )
    (net (code "25") (name "Net-(DS1-C)") (class "Default")
      (node (ref "DS1") (pin "4") (pinfunction "C_4") (pintype "input"))
      (node (ref "R3") (pin "2") (pinfunction "2_2") (pintype "input"))
    )
    (net (code "26") (name "Net-(DS1-D)") (class "Default")
      (node (ref "DS1") (pin "2") (pinfunction "D_2") (pintype "input"))
      (node (ref "R4") (pin "2") (pinfunction "2_2") (pintype "input"))
    )
    (net (code "27") (name "Net-(DS1-DIG1)") (class "Default")
      (node (ref "DS1") (pin "12") (pinfunction "DIG1_12") (pintype "input"))
      (node (ref "Q1") (pin "3") (pinfunction "C_3") (pintype "input"))
    )
    (net (code "28") (name "Net-(DS1-DIG2)") (class "Default")
      (node (ref "DS1") (pin "9") (pinfunction "DIG2_9") (pintype "input"))
      (node (ref "Q2") (pin "3") (pinfunction "C_3") (pintype "input"))
    )
    (net (code "29") (name "Net-(DS1-DIG3)") (class "Default")
      (node (ref "DS1") (pin "8") (pinfunction "DIG3_8") (pintype "input"))
      (node (ref "Q3") (pin "3") (pinfunction "C_3") (pintype "input"))
    )
    (net (code "30") (name "Net-(DS1-DIG4)") (class "Default")
      (node (ref "DS1") (pin "6") (pinfunction "DIG4_6") (pintype "input"))
      (node (ref "Q4") (pin "3") (pinfunction "C_3") (pintype "input"))
    )
    (net (code "31") (name "Net-(DS1-DP)") (class "Default")
      (node (ref "DS1") (pin "3") (pinfunction "DP_3") (pintype "input"))
      (node (ref "R8") (pin "2") (pinfunction "2_2") (pintype "input"))
    )
    (net (code "32") (name "Net-(DS1-E)") (class "Default")
      (node (ref "DS1") (pin "1") (pinfunction "E_1") (pintype "input"))
      (node (ref "R5") (pin "2") (pinfunction "2_2") (pintype "input"))
    )
    (net (code "33") (name "Net-(DS1-F)") (class "Default")
      (node (ref "DS1") (pin "10") (pinfunction "F_10") (pintype "input"))
      (node (ref "R6") (pin "2") (pinfunction "2_2") (pintype "input"))
    )
    (net (code "34") (name "Net-(DS1-G)") (class "Default")
      (node (ref "DS1") (pin "5") (pinfunction "G_5") (pintype "input"))
      (node (ref "R7") (pin "2") (pinfunction "2_2") (pintype "input"))
    )
    (net (code "35") (name "Net-(H2-Pad1)") (class "Default")
      (node (ref "H2") (pin "1") (pinfunction "1_1") (pintype "unspecified"))
      (node (ref "R32") (pin "2") (pinfunction "2_2") (pintype "input"))
    )
    (net (code "36") (name "Net-(H2-Pad4)") (class "Default")
      (node (ref "H2") (pin "4") (pinfunction "4_4") (pintype "unspecified"))
      (node (ref "R33") (pin "2") (pinfunction "2_2") (pintype "input"))
    )
    (net (code "37") (name "Net-(LED2-Pad3)") (class "Default")
      (node (ref "LED2") (pin "3") (pinfunction "3_3") (pintype "unspecified"))
      (node (ref "R23") (pin "1") (pinfunction "1_1") (pintype "input"))
    )
    (net (code "38") (name "Net-(LED4-A)") (class "Default")
      (node (ref "LED4") (pin "2") (pinfunction "A_2") (pintype "input"))
      (node (ref "R20") (pin "2") (pinfunction "2_2") (pintype "input"))
    )
    (net (code "39") (name "Net-(LED4-C)") (class "Default")
      (node (ref "LED4") (pin "1") (pinfunction "C_1") (pintype "input"))
      (node (ref "LED5") (pin "2") (pinfunction "A_2") (pintype "input"))
      (node (ref "U13") (pin "1") (pinfunction "STAT_1") (pintype "input"))
    )
    (net (code "40") (name "Net-(LED5-C)") (class "Default")
      (node (ref "LED5") (pin "1") (pinfunction "C_1") (pintype "input"))
      (node (ref "R19") (pin "2") (pinfunction "2_2") (pintype "input"))
    )
    (net (code "41") (name "Net-(Q1-B)") (class "Default")
      (node (ref "Q1") (pin "1") (pinfunction "B_1") (pintype "input"))
      (node (ref "R24") (pin "2") (pinfunction "2_2") (pintype "input"))
    )
    (net (code "42") (name "Net-(Q2-B)") (class "Default")
      (node (ref "Q2") (pin "1") (pinfunction "B_1") (pintype "input"))
      (node (ref "R25") (pin "2") (pinfunction "2_2") (pintype "input"))
    )
    (net (code "43") (name "Net-(Q3-B)") (class "Default")
      (node (ref "Q3") (pin "1") (pinfunction "B_1") (pintype "input"))
      (node (ref "R26") (pin "2") (pinfunction "2_2") (pintype "input"))
    )
    (net (code "44") (name "Net-(Q4-B)") (class "Default")
      (node (ref "Q4") (pin "1") (pinfunction "B_1") (pintype "input"))
      (node (ref "R27") (pin "2") (pinfunction "2_2") (pintype "input"))
    )
    (net (code "45") (name "Net-(Q5-S)") (class "Default")
      (node (ref "Q5") (pin "2") (pinfunction "S_2") (pintype "input"))
      (node (ref "R31") (pin "1") (pinfunction "1_1") (pintype "input"))
    )
    (net (code "46") (name "Net-(SPK1-+)") (class "Default")
      (node (ref "SPK1") (pin "1") (pinfunction "+_1") (pintype "input"))
      (node (ref "U11") (pin "18") (pinfunction "PWM-_18") (pintype "input"))
    )
    (net (code "47") (name "Net-(SPK1--)") (class "Default")
      (node (ref "SPK1") (pin "2") (pinfunction "-_2") (pintype "input"))
      (node (ref "U11") (pin "16") (pinfunction "PWM+/DAC#_16") (pintype "input"))
    )
    (net (code "48") (name "Net-(U3-RSTb)") (class "Default")
      (node (ref "R21") (pin "1") (pinfunction "1_1") (pintype "input"))
      (node (ref "U3") (pin "9") (pinfunction "RSTb_9") (pintype "unspecified"))
    )
    (net (code "49") (name "Net-(U6-VDD)") (class "Default")
      (node (ref "C25") (pin "2") (pinfunction "2_2") (pintype "input"))
      (node (ref "C27") (pin "2") (pinfunction "2_2") (pintype "input"))
      (node (ref "R28") (pin "2") (pinfunction "2_2") (pintype "input"))
      (node (ref "U6") (pin "1") (pinfunction "VDD_1") (pintype "unspecified"))
    )
    (net (code "50") (name "Net-(U10-BOOT0)") (class "Default")
      (node (ref "R22") (pin "1") (pinfunction "1_1") (pintype "input"))
      (node (ref "U10") (pin "44") (pinfunction "BOOT0_44") (pintype "unspecified"))
    )
    (net (code "51") (name "Net-(U10-NRST)") (class "Default")
      (node (ref "C22") (pin "2") (pinfunction "2_2") (pintype "input"))
      (node (ref "U10") (pin "7") (pinfunction "NRST_7") (pintype "unspecified"))
    )
    (net (code "52") (name "Net-(U10-PA13)") (class "Default")
      (node (ref "R33") (pin "1") (pinfunction "1_1") (pintype "input"))
      (node (ref "U10") (pin "34") (pinfunction "PA13_34") (pintype "unspecified"))
    )
    (net (code "53") (name "Net-(U10-PA14)") (class "Default")
      (node (ref "R32") (pin "1") (pinfunction "1_1") (pintype "input"))
      (node (ref "U10") (pin "37") (pinfunction "PA14_37") (pintype "unspecified"))
    )
    (net (code "54") (name "Net-(U10-PC14-OSC32IN)") (class "Default")
      (node (ref "C20") (pin "2") (pinfunction "2_2") (pintype "input"))
      (node (ref "U10") (pin "3") (pinfunction "PC14-OSC32IN_3") (pintype "unspecified"))
      (node (ref "X1") (pin "1") (pinfunction "1_1") (pintype "unspecified"))
    )
    (net (code "55") (name "Net-(U10-PC15-OSC32OUT)") (class "Default")
      (node (ref "C21") (pin "2") (pinfunction "2_2") (pintype "input"))
      (node (ref "U10") (pin "4") (pinfunction "PC15-OSC32OUT_4") (pintype "unspecified"))
      (node (ref "X1") (pin "2") (pinfunction "2_2") (pintype "unspecified"))
    )
    (net (code "56") (name "Net-(U10-VBAT)") (class "Default")
      (node (ref "H3") (pin "2") (pinfunction "2_2") (pintype "input"))
      (node (ref "U10") (pin "1") (pinfunction "VBAT_1") (pintype "unspecified"))
    )
    (net (code "57") (name "Net-(U10-VDDA)") (class "Default")
      (node (ref "R13") (pin "2") (pinfunction "2_2") (pintype "input"))
      (node (ref "U10") (pin "9") (pinfunction "VDDA_9") (pintype "unspecified"))
    )
    (net (code "58") (name "Net-(U11-CVDD)") (class "Default")
      (node (ref "C1") (pin "1") (pinfunction "1_1") (pintype "input"))
      (node (ref "U11") (pin "12") (pinfunction "CVDD_12") (pintype "input"))
    )
    (net (code "59") (name "Net-(U11-OSCI)") (class "Default")
      (node (ref "R11") (pin "1") (pinfunction "1_1") (pintype "input"))
      (node (ref "U11") (pin "13") (pinfunction "OSCI_13") (pintype "input"))
    )
    (net (code "60") (name "Net-(U12-IO2)") (class "Default")
      (node (ref "C7") (pin "2") (pinfunction "2_2") (pintype "input"))
      (node (ref "U12") (pin "3") (pinfunction "IO2_3") (pintype "unspecified"))
    )
    (net (code "61") (name "Net-(U13-PROG)") (class "Default")
      (node (ref "R18") (pin "1") (pinfunction "1_1") (pintype "input"))
      (node (ref "U13") (pin "4") (pinfunction "PROG_4") (pintype "input"))
    )
    (net (code "62") (name "Net-(U13-VBAT)") (class "Default")
      (node (ref "C13") (pin "1") (pinfunction "1_1") (pintype "input"))
      (node (ref "CN1") (pin "1") (pinfunction "1_1") (pintype "unspecified"))
      (node (ref "U13") (pin "3") (pinfunction "VBAT_3") (pintype "input"))
    )
    (net (code "63") (name "Net-(USB1-CC1)") (class "Default")
      (node (ref "R9") (pin "2") (pinfunction "2_2") (pintype "input"))
      (node (ref "USB1") (pin "A5") (pinfunction "CC1_A5") (pintype "input"))
    )
    (net (code "64") (name "Net-(USB1-CC2)") (class "Default")
      (node (ref "R10") (pin "2") (pinfunction "2_2") (pintype "input"))
      (node (ref "USB1") (pin "B5") (pinfunction "CC2_B5") (pintype "input"))
    )
    (net (code "65") (name "PWR_EN") (class "Default")
      (node (ref "Q5") (pin "3") (pinfunction "D_3") (pintype "input"))
      (node (ref "U10") (pin "38") (pinfunction "PA15_38") (pintype "unspecified"))
    )
    (net (code "66") (name "RES_PHOTO") (class "Default")
      (node (ref "R34") (pin "2") (pinfunction "2_2") (pintype "input"))
      (node (ref "R35") (pin "1") (pinfunction "1_1") (pintype "input"))
      (node (ref "U10") (pin "14") (pinfunction "PA4_14") (pintype "unspecified"))
    )
    (net (code "67") (name "RXD") (class "Default")
      (node (ref "U10") (pin "21") (pinfunction "PB10_21") (pintype "unspecified"))
      (node (ref "U3") (pin "20") (pinfunction "RXD_20") (pintype "unspecified"))
    )
    (net (code "68") (name "SEGA") (class "Default")
      (node (ref "R1") (pin "1") (pinfunction "1_1") (pintype "input"))
      (node (ref "U10") (pin "18") (pinfunction "PB0_18") (pintype "unspecified"))
    )
    (net (code "69") (name "SEGB") (class "Default")
      (node (ref "R2") (pin "1") (pinfunction "1_1") (pintype "input"))
      (node (ref "U10") (pin "19") (pinfunction "PB1_19") (pintype "unspecified"))
    )
    (net (code "70") (name "SEGC") (class "Default")
      (node (ref "R3") (pin "1") (pinfunction "1_1") (pintype "input"))
      (node (ref "U10") (pin "20") (pinfunction "PB2_20") (pintype "unspecified"))
    )
    (net (code "71") (name "SEGD") (class "Default")
      (node (ref "R4") (pin "1") (pinfunction "1_1") (pintype "input"))
      (node (ref "U10") (pin "39") (pinfunction "PB3_39") (pintype "unspecified"))
    )
    (net (code "72") (name "SEGDP") (class "Default")
      (node (ref "R8") (pin "1") (pinfunction "1_1") (pintype "input"))
      (node (ref "U10") (pin "43") (pinfunction "PB7_43") (pintype "unspecified"))
    )
    (net (code "73") (name "SEGE") (class "Default")
      (node (ref "R5") (pin "1") (pinfunction "1_1") (pintype "input"))
      (node (ref "U10") (pin "40") (pinfunction "PB4_40") (pintype "unspecified"))
    )
    (net (code "74") (name "SEGF") (class "Default")
      (node (ref "R6") (pin "1") (pinfunction "1_1") (pintype "input"))
      (node (ref "U10") (pin "41") (pinfunction "PB5_41") (pintype "unspecified"))
    )
    (net (code "75") (name "SEGG") (class "Default")
      (node (ref "R7") (pin "1") (pinfunction "1_1") (pintype "input"))
      (node (ref "U10") (pin "42") (pinfunction "PB6_42") (pintype "unspecified"))
    )
    (net (code "76") (name "SPI_CS_AM") (class "Default")
      (node (ref "H1") (pin "1") (pinfunction "1_1") (pintype "unspecified"))
      (node (ref "U11") (pin "3") (pinfunction "P15_3") (pintype "input"))
      (node (ref "U12") (pin "1") (pinfunction "CS#_1") (pintype "unspecified"))
    )
    (net (code "77") (name "SPI_MISO") (class "Default")
      (node (ref "H1") (pin "2") (pinfunction "2_2") (pintype "unspecified"))
      (node (ref "U11") (pin "1") (pinfunction "P13_1") (pintype "input"))
      (node (ref "U12") (pin "2") (pinfunction "DO（IO1）_2") (pintype "unspecified"))
    )
    (net (code "78") (name "SPI_MOSI") (class "Default")
      (node (ref "H1") (pin "4") (pinfunction "4_4") (pintype "unspecified"))
      (node (ref "U11") (pin "2") (pinfunction "P14_2") (pintype "input"))
      (node (ref "U12") (pin "5") (pinfunction "DI（IO0）_5") (pintype "unspecified"))
    )
    (net (code "79") (name "SPI_SCK") (class "Default")
      (node (ref "H1") (pin "3") (pinfunction "3_3") (pintype "unspecified"))
      (node (ref "U11") (pin "4") (pinfunction "P16_4") (pintype "input"))
      (node (ref "U12") (pin "6") (pinfunction "CLK_6") (pintype "unspecified"))
    )
    (net (code "80") (name "TXD") (class "Default")
      (node (ref "U10") (pin "22") (pinfunction "PB11_22") (pintype "unspecified"))
      (node (ref "U3") (pin "21") (pinfunction "TXD_21") (pintype "unspecified"))
    )
    (net (code "81") (name "USB_DN") (class "Default")
      (node (ref "U3") (pin "4") (pinfunction "D-_4") (pintype "unspecified"))
      (node (ref "USB1") (pin "A7") (pinfunction "DN1_A7") (pintype "input"))
      (node (ref "USB1") (pin "B7") (pinfunction "DN2_B7") (pintype "input"))
    )
    (net (code "82") (name "USB_DP") (class "Default")
      (node (ref "U3") (pin "3") (pinfunction "D+_3") (pintype "unspecified"))
      (node (ref "USB1") (pin "A6") (pinfunction "DP1_A6") (pintype "input"))
      (node (ref "USB1") (pin "B6") (pinfunction "DP2_B6") (pintype "input"))
    )
    (net (code "83") (name "VBAT") (class "Default")
      (node (ref "C15") (pin "2") (pinfunction "2_2") (pintype "input"))
      (node (ref "C16") (pin "2") (pinfunction "2_2") (pintype "input"))
      (node (ref "U15") (pin "1") (pinfunction "IN_1") (pintype "unspecified"))
      (node (ref "U15") (pin "3") (pinfunction "EN_3") (pintype "unspecified"))
    )
    (net (code "84") (name "VBUS") (class "Default")
      (node (ref "C14") (pin "1") (pinfunction "1_1") (pintype "input"))
      (node (ref "R20") (pin "1") (pinfunction "1_1") (pintype "input"))
      (node (ref "U13") (pin "5") (pinfunction "VDD_5") (pintype "input"))
      (node (ref "U3") (pin "7") (pinfunction "VREGIN_7") (pintype "unspecified"))
      (node (ref "U3") (pin "8") (pinfunction "VBUS_8") (pintype "unspecified"))
      (node (ref "USB1") (pin "A4") (pinfunction "VBUS_A4") (pintype "input"))
      (node (ref "USB1") (pin "A9") (pinfunction "VBUS_A9") (pintype "input"))
      (node (ref "USB1") (pin "B4") (pinfunction "VBUS_B4") (pintype "input"))
      (node (ref "USB1") (pin "B9") (pinfunction "VBUS_B9") (pintype "input"))
    )
    (net (code "85") (name "unconnected-(U3-CTS-Pad18)") (class "Default")
      (node (ref "U3") (pin "18") (pinfunction "CTS_18") (pintype "unspecified+no_connect"))
    )
    (net (code "86") (name "unconnected-(U3-DCD-Pad24)") (class "Default")
      (node (ref "U3") (pin "24") (pinfunction "DCD_24") (pintype "unspecified+no_connect"))
    )
    (net (code "87") (name "unconnected-(U3-DSR-Pad22)") (class "Default")
      (node (ref "U3") (pin "22") (pinfunction "DSR_22") (pintype "unspecified+no_connect"))
    )
    (net (code "88") (name "unconnected-(U3-DTR-Pad23)") (class "Default")
      (node (ref "U3") (pin "23") (pinfunction "DTR_23") (pintype "unspecified+no_connect"))
    )
    (net (code "89") (name "unconnected-(U3-GPIO.0{slash}TXT-Pad14)") (class "Default")
      (node (ref "U3") (pin "14") (pinfunction "GPIO.0/TXT_14") (pintype "unspecified+no_connect"))
    )
    (net (code "90") (name "unconnected-(U3-GPIO.1{slash}RXT-Pad13)") (class "Default")
      (node (ref "U3") (pin "13") (pinfunction "GPIO.1/RXT_13") (pintype "unspecified+no_connect"))
    )
    (net (code "91") (name "unconnected-(U3-GPIO.2{slash}RS485-Pad12)") (class "Default")
      (node (ref "U3") (pin "12") (pinfunction "GPIO.2/RS485_12") (pintype "unspecified+no_connect"))
    )
    (net (code "92") (name "unconnected-(U3-GPIO.3{slash}WAKEUP-Pad11)") (class "Default")
      (node (ref "U3") (pin "11") (pinfunction "GPIO.3/WAKEUP_11") (pintype "unspecified+no_connect"))
    )
    (net (code "93") (name "unconnected-(U3-NC-Pad10)") (class "Default")
      (node (ref "U3") (pin "10") (pinfunction "NC_10") (pintype "unspecified+no_connect"))
    )
    (net (code "94") (name "unconnected-(U3-NC-Pad16)") (class "Default")
      (node (ref "U3") (pin "16") (pinfunction "NC_16") (pintype "unspecified+no_connect"))
    )
    (net (code "95") (name "unconnected-(U3-RI{slash}CLK-Pad1)") (class "Default")
      (node (ref "U3") (pin "1") (pinfunction "RI/CLK_1") (pintype "unspecified+no_connect"))
    )
    (net (code "96") (name "unconnected-(U3-RTS-Pad19)") (class "Default")
      (node (ref "U3") (pin "19") (pinfunction "RTS_19") (pintype "unspecified+no_connect"))
    )
    (net (code "97") (name "unconnected-(U3-SUSPEND-Pad17)") (class "Default")
      (node (ref "U3") (pin "17") (pinfunction "SUSPEND_17") (pintype "unspecified+no_connect"))
    )
    (net (code "98") (name "unconnected-(U3-SUSPENDb-Pad15)") (class "Default")
      (node (ref "U3") (pin "15") (pinfunction "SUSPENDb_15") (pintype "unspecified+no_connect"))
    )
    (net (code "99") (name "unconnected-(U5-NC-Pad3)") (class "Default")
      (node (ref "U5") (pin "3") (pinfunction "NC_3") (pintype "unspecified+no_connect"))
    )
    (net (code "100") (name "unconnected-(U5-NC-Pad4)") (class "Default")
      (node (ref "U5") (pin "4") (pinfunction "NC_4") (pintype "unspecified+no_connect"))
    )
    (net (code "101") (name "unconnected-(U6-n{slash}a-Pad4)") (class "Default")
      (node (ref "U6") (pin "4") (pinfunction "n/a_4") (pintype "unspecified+no_connect"))
    )
    (net (code "102") (name "unconnected-(U10-PC13-TAMPER-RTC-Pad2)") (class "Default")
      (node (ref "U10") (pin "2") (pinfunction "PC13-TAMPER-RTC_2") (pintype "unspecified+no_connect"))
    )
    (net (code "103") (name "unconnected-(U10-PD0-OSCIN-Pad5)") (class "Default")
      (node (ref "U10") (pin "5") (pinfunction "PD0-OSCIN_5") (pintype "unspecified+no_connect"))
    )
    (net (code "104") (name "unconnected-(U10-PD1-OSCOUT-Pad6)") (class "Default")
      (node (ref "U10") (pin "6") (pinfunction "PD1-OSCOUT_6") (pintype "unspecified+no_connect"))
    )
    (net (code "105") (name "unconnected-(U11-NC-Pad20)") (class "Default")
      (node (ref "U11") (pin "20") (pinfunction "NC_20") (pintype "input+no_connect"))
    )
    (net (code "106") (name "unconnected-(U11-P00-Pad6)") (class "Default")
      (node (ref "U11") (pin "6") (pinfunction "P00_6") (pintype "input+no_connect"))
    )
    (net (code "107") (name "unconnected-(U15-NC-Pad4)") (class "Default")
      (node (ref "U15") (pin "4") (pinfunction "NC_4") (pintype "unspecified+no_connect"))
    )
    (net (code "108") (name "unconnected-(USB1-SBUS1-PadA8)") (class "Default")
      (node (ref "USB1") (pin "A8") (pinfunction "SBUS1_A8") (pintype "input+no_connect"))
    )
    (net (code "109") (name "unconnected-(USB1-SBUS2-PadB8)") (class "Default")
      (node (ref "USB1") (pin "B8") (pinfunction "SBUS2_B8") (pintype "input+no_connect"))
    )
  )
)
